# Proximity_sensor_v1p0.net
KiCad netlist of a schematic drawn in EAGLE
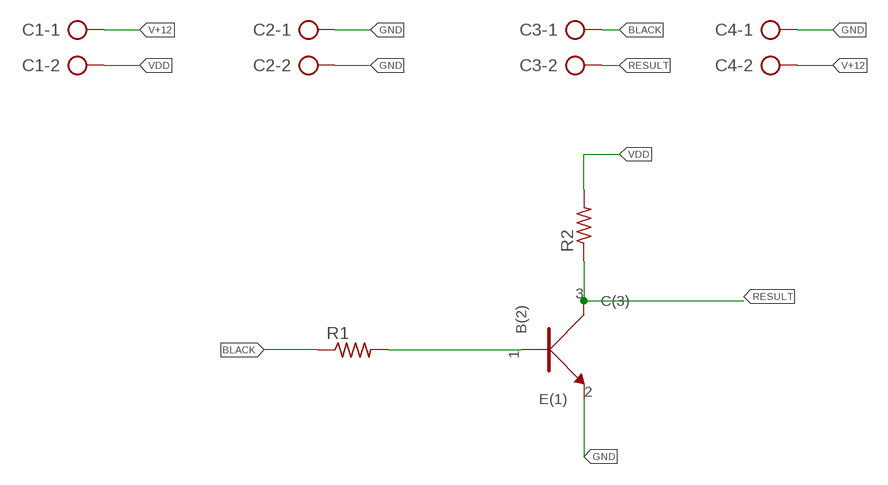
[diagram p0: schematic, sheet 1]

(export (version "E")
  (design (tool "Eeschema 10.0.6"))
  (components
    (comp (ref "C1")
      (value "AK300/2")
      (footprint "eagle-import:AK300_2")
      (libsource (lib "eagle-import") (part "AK300/2"))
    )
    (comp (ref "C2")
      (value "AK300/2")
      (footprint "eagle-import:AK300_2")
      (libsource (lib "eagle-import") (part "AK300/2"))
    )
    (comp (ref "C3")
      (value "AK300/2")
      (footprint "eagle-import:AK300_2")
      (libsource (lib "eagle-import") (part "AK300/2"))
    )
    (comp (ref "C4")
      (value "AK300/2")
      (footprint "eagle-import:AK300_2")
      (libsource (lib "eagle-import") (part "AK300/2"))
    )
    (comp (ref "R1")
      (value "R_0805")
      (footprint "eagle-import:0805")
      (libsource (lib "eagle-import") (part "R_0805"))
    )
    (comp (ref "R2")
      (value "R_0805")
      (footprint "eagle-import:0805")
      (libsource (lib "eagle-import") (part "R_0805"))
    )
    (comp (ref "U1")
      (value "BC846BW")
      (footprint "eagle-import:SOT323")
      (libsource (lib "eagle-import") (part "BC846BW"))
    )
  )
  (nets
    (net (code "1") (name "BLACK") (class "Default")
      (node (ref "C3") (pin "1") (pinfunction "KL_1") (pintype "passive"))
      (node (ref "R1") (pin "1") (pinfunction "1_1") (pintype "passive"))
    )
    (net (code "2") (name "GND") (class "Default")
      (node (ref "C2") (pin "1") (pinfunction "KL_1") (pintype "passive"))
      (node (ref "C2") (pin "2") (pinfunction "KL_2") (pintype "passive"))
      (node (ref "C4") (pin "1") (pinfunction "KL_1") (pintype "passive"))
      (node (ref "U1") (pin "2") (pinfunction "E(1)_2") (pintype "output"))
    )
    (net (code "3") (name "Net-(U1-B(2))") (class "Default")
      (node (ref "R1") (pin "2") (pinfunction "2_2") (pintype "passive"))
      (node (ref "U1") (pin "1") (pinfunction "B(2)_1") (pintype "input"))
    )
    (net (code "4") (name "RESULT") (class "Default")
      (node (ref "C3") (pin "2") (pinfunction "KL_2") (pintype "passive"))
      (node (ref "R2") (pin "1") (pinfunction "1_1") (pintype "passive"))
      (node (ref "U1") (pin "3") (pinfunction "C(3)_3") (pintype "input"))
    )
    (net (code "5") (name "V+12") (class "Default")
      (node (ref "C1") (pin "1") (pinfunction "KL_1") (pintype "passive"))
      (node (ref "C4") (pin "2") (pinfunction "KL_2") (pintype "passive"))
    )
    (net (code "6") (name "VDD") (class "Default")
      (node (ref "C1") (pin "2") (pinfunction "KL_2") (pintype "passive"))
      (node (ref "R2") (pin "2") (pinfunction "2_2") (pintype "passive"))
    )
  )
)
